# MIPI_Interface.net
KiCad netlist of a schematic drawn in Altium Designer
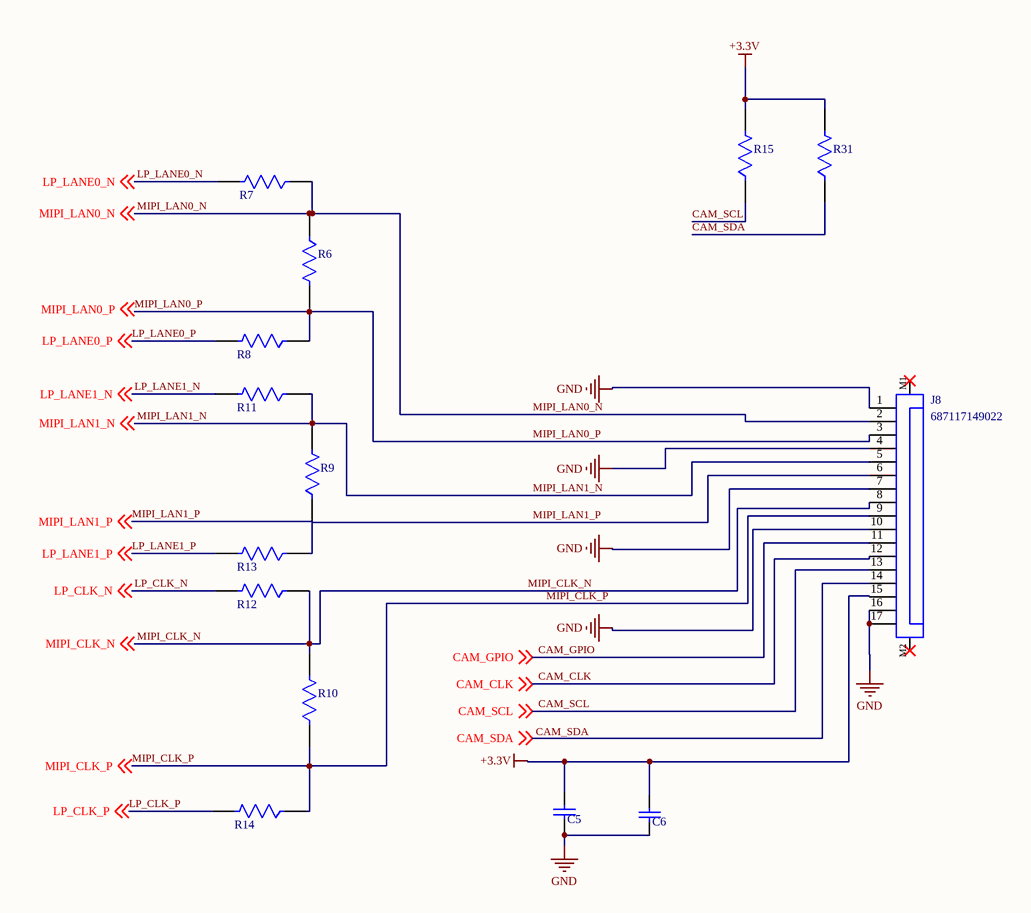
[diagram p0: MIPI_Interface.SchDoc]

(export (version "E")
  (design (tool "Eeschema 10.0.6"))
  (components
    (comp (ref "C5")
      (value "VJ0805Y152KXAAC")
      (footprint "CAPC2013X145X48NL20T23")
      (fields (field (name "MANUFACTURER") "Vitramon"))
      (libsource (lib "Altium Content Vault") (part "CAP"))
    )
    (comp (ref "C6")
      (value "VJ0805Y152KXAAC")
      (footprint "CAPC2013X145X48NL20T23")
      (fields (field (name "MANUFACTURER") "Vitramon"))
      (libsource (lib "Altium Content Vault") (part "CAP"))
    )
    (comp (ref "J8")
      (value "687117149022")
      (footprint "687117149022")
      (description "SMT ZIF Connectors Hinge Type WR-FPC, Horizontal, Bottom Contact, pitch 0.5 mm, 17 pins")
      (libsource (lib "Altium Content Vault") (part "FPC - 17P - 2MP"))
    )
    (comp (ref "R6")
      (value "MCU0805MD4991BP100")
      (footprint "FP-MCU0805-MFG")
      (description "RES 1.05K OHM 0.5% 1/5W 0805")
      (fields (field (name "TOLERANCE") "0.1%"))
      (libsource (lib "Altium Content Vault") (part "1029c3af85768c4190bb7ad29bc67b5"))
    )
    (comp (ref "R7")
      (value "MCU0805MD4991BP100")
      (footprint "FP-MCU0805-MFG")
      (description "RES 1.05K OHM 0.5% 1/5W 0805")
      (fields (field (name "TOLERANCE") "0.1%"))
      (libsource (lib "Altium Content Vault") (part "1029c3af85768c4190bb7ad29bc67b5"))
    )
    (comp (ref "R8")
      (value "MCU0805MD4991BP100")
      (footprint "FP-MCU0805-MFG")
      (description "RES 1.05K OHM 0.5% 1/5W 0805")
      (fields (field (name "TOLERANCE") "0.1%"))
      (libsource (lib "Altium Content Vault") (part "1029c3af85768c4190bb7ad29bc67b5"))
    )
    (comp (ref "R9")
      (value "MCU0805MD4991BP100")
      (footprint "FP-MCU0805-MFG")
      (description "RES 1.05K OHM 0.5% 1/5W 0805")
      (fields (field (name "TOLERANCE") "0.1%"))
      (libsource (lib "Altium Content Vault") (part "1029c3af85768c4190bb7ad29bc67b5"))
    )
    (comp (ref "R10")
      (value "MCU0805MD4991BP100")
      (footprint "FP-MCU0805-MFG")
      (description "RES 1.05K OHM 0.5% 1/5W 0805")
      (fields (field (name "TOLERANCE") "0.1%"))
      (libsource (lib "Altium Content Vault") (part "1029c3af85768c4190bb7ad29bc67b5"))
    )
    (comp (ref "R11")
      (value "MCU0805MD4991BP100")
      (footprint "FP-MCU0805-MFG")
      (description "RES 1.05K OHM 0.5% 1/5W 0805")
      (fields (field (name "TOLERANCE") "0.1%"))
      (libsource (lib "Altium Content Vault") (part "1029c3af85768c4190bb7ad29bc67b5"))
    )
    (comp (ref "R12")
      (value "MCU0805MD4991BP100")
      (footprint "FP-MCU0805-MFG")
      (description "RES 1.05K OHM 0.5% 1/5W 0805")
      (fields (field (name "TOLERANCE") "0.1%"))
      (libsource (lib "Altium Content Vault") (part "1029c3af85768c4190bb7ad29bc67b5"))
    )
    (comp (ref "R13")
      (value "MCU0805MD4991BP100")
      (footprint "FP-MCU0805-MFG")
      (description "RES 1.05K OHM 0.5% 1/5W 0805")
      (fields (field (name "TOLERANCE") "0.1%"))
      (libsource (lib "Altium Content Vault") (part "1029c3af85768c4190bb7ad29bc67b5"))
    )
    (comp (ref "R14")
      (value "MCU0805MD4991BP100")
      (footprint "FP-MCU0805-MFG")
      (description "RES 1.05K OHM 0.5% 1/5W 0805")
      (fields (field (name "TOLERANCE") "0.1%"))
      (libsource (lib "Altium Content Vault") (part "1029c3af85768c4190bb7ad29bc67b5"))
    )
    (comp (ref "R15")
      (value "MCU0805MD4991BP100")
      (footprint "FP-MCU0805-MFG")
      (description "RES 1.05K OHM 0.5% 1/5W 0805")
      (fields (field (name "TOLERANCE") "0.1%"))
      (libsource (lib "Altium Content Vault") (part "1029c3af85768c4190bb7ad29bc67b5"))
    )
    (comp (ref "R31")
      (value "MCU0805MD4991BP100")
      (footprint "FP-MCU0805-MFG")
      (description "RES 1.05K OHM 0.5% 1/5W 0805")
      (fields (field (name "TOLERANCE") "0.1%"))
      (libsource (lib "Altium Content Vault") (part "1029c3af85768c4190bb7ad29bc67b5"))
    )
  )
  (nets
    (net (code "1") (name "+3.3V") (class "Default")
      (node (ref "C5") (pin "2") (pinfunction "2_2") (pintype "passive"))
      (node (ref "C6") (pin "2") (pinfunction "2_2") (pintype "passive"))
      (node (ref "J8") (pin "15") (pinfunction "15_15") (pintype "passive"))
      (node (ref "R15") (pin "2") (pinfunction "2_2") (pintype "passive"))
      (node (ref "R31") (pin "2") (pinfunction "2_2") (pintype "passive"))
    )
    (net (code "2") (name "CAM_CLK") (class "Default")
      (node (ref "J8") (pin "12") (pinfunction "12_12") (pintype "passive"))
    )
    (net (code "3") (name "CAM_GPIO") (class "Default")
      (node (ref "J8") (pin "11") (pinfunction "11_11") (pintype "passive"))
    )
    (net (code "4") (name "CAM_SCL") (class "Default")
      (node (ref "J8") (pin "13") (pinfunction "13_13") (pintype "passive"))
      (node (ref "R15") (pin "1") (pinfunction "1_1") (pintype "passive"))
    )
    (net (code "5") (name "CAM_SDA") (class "Default")
      (node (ref "J8") (pin "14") (pinfunction "14_14") (pintype "passive"))
      (node (ref "R31") (pin "1") (pinfunction "1_1") (pintype "passive"))
    )
    (net (code "6") (name "GND") (class "Default")
      (node (ref "C5") (pin "1") (pinfunction "1_1") (pintype "passive"))
      (node (ref "C6") (pin "1") (pinfunction "1_1") (pintype "passive"))
      (node (ref "J8") (pin "1") (pinfunction "1_1") (pintype "passive"))
      (node (ref "J8") (pin "10") (pinfunction "10_10") (pintype "passive"))
      (node (ref "J8") (pin "16") (pinfunction "16_16") (pintype "passive"))
      (node (ref "J8") (pin "17") (pinfunction "17_17") (pintype "passive"))
      (node (ref "J8") (pin "4") (pinfunction "4_4") (pintype "passive"))
      (node (ref "J8") (pin "7") (pinfunction "7_7") (pintype "passive"))
    )
    (net (code "7") (name "LP_CLK_N") (class "Default")
      (node (ref "R12") (pin "2") (pinfunction "2_2") (pintype "passive"))
    )
    (net (code "8") (name "LP_CLK_P") (class "Default")
      (node (ref "R14") (pin "2") (pinfunction "2_2") (pintype "passive"))
    )
    (net (code "9") (name "LP_LANE0_N") (class "Default")
      (node (ref "R7") (pin "2") (pinfunction "2_2") (pintype "passive"))
    )
    (net (code "10") (name "LP_LANE0_P") (class "Default")
      (node (ref "R8") (pin "2") (pinfunction "2_2") (pintype "passive"))
    )
    (net (code "11") (name "LP_LANE1_N") (class "Default")
      (node (ref "R11") (pin "2") (pinfunction "2_2") (pintype "passive"))
    )
    (net (code "12") (name "LP_LANE1_P") (class "Default")
      (node (ref "R13") (pin "2") (pinfunction "2_2") (pintype "passive"))
    )
    (net (code "13") (name "MIPI_CLK_N") (class "Default")
      (node (ref "J8") (pin "8") (pinfunction "8_8") (pintype "passive"))
      (node (ref "R10") (pin "2") (pinfunction "2_2") (pintype "passive"))
      (node (ref "R12") (pin "1") (pinfunction "1_1") (pintype "passive"))
    )
    (net (code "14") (name "MIPI_CLK_P") (class "Default")
      (node (ref "J8") (pin "9") (pinfunction "9_9") (pintype "passive"))
      (node (ref "R10") (pin "1") (pinfunction "1_1") (pintype "passive"))
      (node (ref "R14") (pin "1") (pinfunction "1_1") (pintype "passive"))
    )
    (net (code "15") (name "MIPI_LAN0_N") (class "Default")
      (node (ref "J8") (pin "2") (pinfunction "2_2") (pintype "passive"))
      (node (ref "R6") (pin "1") (pinfunction "1_1") (pintype "passive"))
      (node (ref "R7") (pin "1") (pinfunction "1_1") (pintype "passive"))
    )
    (net (code "16") (name "MIPI_LAN0_P") (class "Default")
      (node (ref "J8") (pin "3") (pinfunction "3_3") (pintype "passive"))
      (node (ref "R6") (pin "2") (pinfunction "2_2") (pintype "passive"))
      (node (ref "R8") (pin "1") (pinfunction "1_1") (pintype "passive"))
    )
    (net (code "17") (name "MIPI_LAN1_N") (class "Default")
      (node (ref "J8") (pin "5") (pinfunction "5_5") (pintype "passive"))
      (node (ref "R11") (pin "1") (pinfunction "1_1") (pintype "passive"))
      (node (ref "R9") (pin "2") (pinfunction "2_2") (pintype "passive"))
    )
    (net (code "18") (name "MIPI_LAN1_P") (class "Default")
      (node (ref "J8") (pin "6") (pinfunction "6_6") (pintype "passive"))
      (node (ref "R13") (pin "1") (pinfunction "1_1") (pintype "passive"))
      (node (ref "R9") (pin "1") (pinfunction "1_1") (pintype "passive"))
    )
    (net (code "19") (name "unconnected-(J8-PadM1)") (class "Default")
      (node (ref "J8") (pin "M1") (pinfunction "M1_M1") (pintype "passive+no_connect"))
    )
    (net (code "20") (name "unconnected-(J8-PadM2)") (class "Default")
      (node (ref "J8") (pin "M2") (pinfunction "M2_M2") (pintype "passive+no_connect"))
    )
  )
)
